# Entrance_v0_2.net
KiCad netlist of a schematic drawn in EAGLE
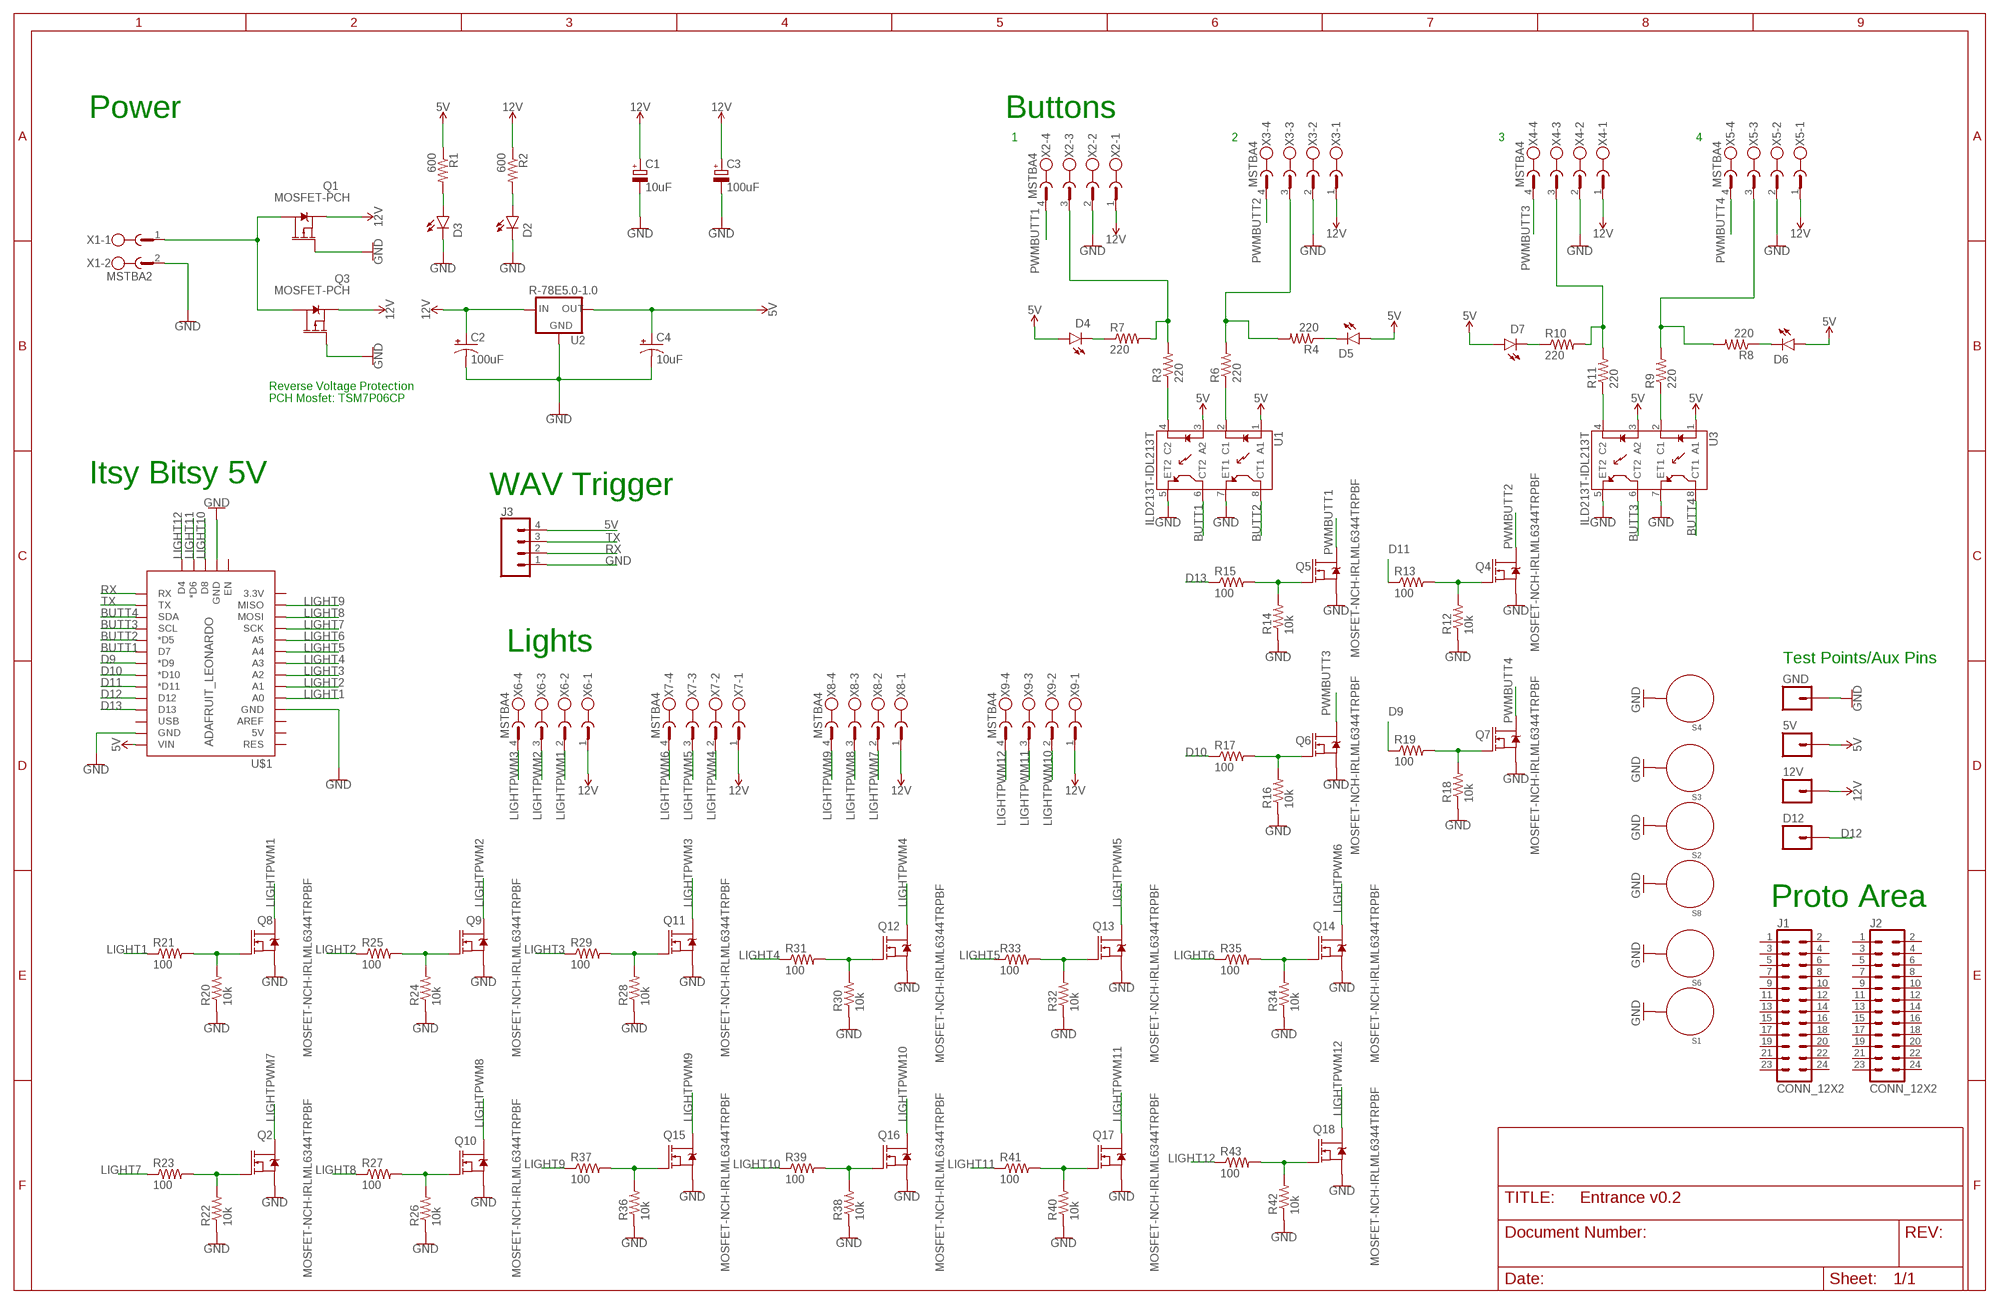
[diagram p0: schematic, sheet 1]

(export (version "E")
  (design (tool "Eeschema 10.0.6"))
  (components
    (comp (ref "5V")
      (value "M01PTH")
      (footprint "eagle-import:1X01")
      (libsource (lib "eagle-import") (part "M01PTH"))
    )
    (comp (ref "12V")
      (value "M01PTH")
      (footprint "eagle-import:1X01")
      (libsource (lib "eagle-import") (part "M01PTH"))
    )
    (comp (ref "C1")
      (value "10uF")
      (footprint "eagle-import:E2-5")
      (libsource (lib "eagle-import") (part "CPOL-EUE2-5"))
    )
    (comp (ref "C2")
      (value "100uF")
      (footprint "eagle-import:CPOL-RADIAL-2.5MM-6.5MM")
      (libsource (lib "eagle-import") (part "100UF-POLAR-RADIAL-2.5MM-25V-20%"))
    )
    (comp (ref "C3")
      (value "100uF")
      (footprint "eagle-import:E3,5-10")
      (libsource (lib "eagle-import") (part "CPOL-EUE3.5-10"))
    )
    (comp (ref "C4")
      (value "10uF")
      (footprint "eagle-import:CPOL-RADIAL-2.5MM-5MM-KIT")
      (libsource (lib "eagle-import") (part "10UF-POLAR-RADIAL-2.5MM-KIT-25V-20%"))
    )
    (comp (ref "D2")
      (value "RED")
      (footprint "eagle-import:SPARKFUN-LED_LED-1206")
      (libsource (lib "eagle-import") (part "SPARKFUN-LED_LED1206"))
    )
    (comp (ref "D3")
      (value "RED")
      (footprint "eagle-import:SPARKFUN-LED_LED-1206")
      (libsource (lib "eagle-import") (part "SPARKFUN-LED_LED1206"))
    )
    (comp (ref "D4")
      (value "RED")
      (footprint "eagle-import:LED-1206")
      (libsource (lib "eagle-import") (part "LED-RED1206"))
    )
    (comp (ref "D5")
      (value "RED")
      (footprint "eagle-import:LED-1206")
      (libsource (lib "eagle-import") (part "LED-RED1206"))
    )
    (comp (ref "D6")
      (value "RED")
      (footprint "eagle-import:LED-1206")
      (libsource (lib "eagle-import") (part "LED-RED1206"))
    )
    (comp (ref "D7")
      (value "RED")
      (footprint "eagle-import:LED-1206")
      (libsource (lib "eagle-import") (part "LED-RED1206"))
    )
    (comp (ref "D12")
      (value "M01PTH")
      (footprint "eagle-import:1X01")
      (libsource (lib "eagle-import") (part "M01PTH"))
    )
    (comp (ref "GND")
      (value "M01PTH")
      (footprint "eagle-import:1X01")
      (libsource (lib "eagle-import") (part "M01PTH"))
    )
    (comp (ref "J1")
      (value "CONN_12X2")
      (footprint "eagle-import:2X12")
      (libsource (lib "eagle-import") (part "CONN_12X2"))
    )
    (comp (ref "J2")
      (value "CONN_12X2")
      (footprint "eagle-import:2X12")
      (libsource (lib "eagle-import") (part "CONN_12X2"))
    )
    (comp (ref "J3")
      (value "CONN_043.5MM_RA")
      (footprint "eagle-import:1X04_3.5MM_RA")
      (libsource (lib "eagle-import") (part "CONN_043.5MM_RA"))
    )
    (comp (ref "Q1")
      (value "MOSFET-PCH")
      (footprint "eagle-import:DPAK@1")
      (libsource (lib "eagle-import") (part "MOSFET-PCH"))
    )
    (comp (ref "Q2")
      (value "MOSFET-NCH-IRLML6344TRPBF")
      (footprint "eagle-import:SOT23-3")
      (libsource (lib "eagle-import") (part "MOSFET-NCH-IRLML6344TRPBF"))
    )
    (comp (ref "Q3")
      (value "MOSFET-PCH")
      (footprint "eagle-import:DPAK@1")
      (libsource (lib "eagle-import") (part "MOSFET-PCH"))
    )
    (comp (ref "Q4")
      (value "MOSFET-NCH-IRLML6344TRPBF")
      (footprint "eagle-import:SOT23-3")
      (libsource (lib "eagle-import") (part "MOSFET-NCH-IRLML6344TRPBF"))
    )
    (comp (ref "Q5")
      (value "MOSFET-NCH-IRLML6344TRPBF")
      (footprint "eagle-import:SOT23-3")
      (libsource (lib "eagle-import") (part "MOSFET-NCH-IRLML6344TRPBF"))
    )
    (comp (ref "Q6")
      (value "MOSFET-NCH-IRLML6344TRPBF")
      (footprint "eagle-import:SOT23-3")
      (libsource (lib "eagle-import") (part "MOSFET-NCH-IRLML6344TRPBF"))
    )
    (comp (ref "Q7")
      (value "MOSFET-NCH-IRLML6344TRPBF")
      (footprint "eagle-import:SOT23-3")
      (libsource (lib "eagle-import") (part "MOSFET-NCH-IRLML6344TRPBF"))
    )
    (comp (ref "Q8")
      (value "MOSFET-NCH-IRLML6344TRPBF")
      (footprint "eagle-import:SOT23-3")
      (libsource (lib "eagle-import") (part "MOSFET-NCH-IRLML6344TRPBF"))
    )
    (comp (ref "Q9")
      (value "MOSFET-NCH-IRLML6344TRPBF")
      (footprint "eagle-import:SOT23-3")
      (libsource (lib "eagle-import") (part "MOSFET-NCH-IRLML6344TRPBF"))
    )
    (comp (ref "Q10")
      (value "MOSFET-NCH-IRLML6344TRPBF")
      (footprint "eagle-import:SOT23-3")
      (libsource (lib "eagle-import") (part "MOSFET-NCH-IRLML6344TRPBF"))
    )
    (comp (ref "Q11")
      (value "MOSFET-NCH-IRLML6344TRPBF")
      (footprint "eagle-import:SOT23-3")
      (libsource (lib "eagle-import") (part "MOSFET-NCH-IRLML6344TRPBF"))
    )
    (comp (ref "Q12")
      (value "MOSFET-NCH-IRLML6344TRPBF")
      (footprint "eagle-import:SOT23-3")
      (libsource (lib "eagle-import") (part "MOSFET-NCH-IRLML6344TRPBF"))
    )
    (comp (ref "Q13")
      (value "MOSFET-NCH-IRLML6344TRPBF")
      (footprint "eagle-import:SOT23-3")
      (libsource (lib "eagle-import") (part "MOSFET-NCH-IRLML6344TRPBF"))
    )
    (comp (ref "Q14")
      (value "MOSFET-NCH-IRLML6344TRPBF")
      (footprint "eagle-import:SOT23-3")
      (libsource (lib "eagle-import") (part "MOSFET-NCH-IRLML6344TRPBF"))
    )
    (comp (ref "Q15")
      (value "MOSFET-NCH-IRLML6344TRPBF")
      (footprint "eagle-import:SOT23-3")
      (libsource (lib "eagle-import") (part "MOSFET-NCH-IRLML6344TRPBF"))
    )
    (comp (ref "Q16")
      (value "MOSFET-NCH-IRLML6344TRPBF")
      (footprint "eagle-import:SOT23-3")
      (libsource (lib "eagle-import") (part "MOSFET-NCH-IRLML6344TRPBF"))
    )
    (comp (ref "Q17")
      (value "MOSFET-NCH-IRLML6344TRPBF")
      (footprint "eagle-import:SOT23-3")
      (libsource (lib "eagle-import") (part "MOSFET-NCH-IRLML6344TRPBF"))
    )
    (comp (ref "Q18")
      (value "MOSFET-NCH-IRLML6344TRPBF")
      (footprint "eagle-import:SOT23-3")
      (libsource (lib "eagle-import") (part "MOSFET-NCH-IRLML6344TRPBF"))
    )
    (comp (ref "R1")
      (value "600")
      (footprint "eagle-import:R0805")
      (libsource (lib "eagle-import") (part "R-US_R0805"))
    )
    (comp (ref "R2")
      (value "600")
      (footprint "eagle-import:R0805")
      (libsource (lib "eagle-import") (part "R-US_R0805"))
    )
    (comp (ref "R3")
      (value "220")
      (footprint "eagle-import:R0805")
      (libsource (lib "eagle-import") (part "R-US_R0805"))
    )
    (comp (ref "R4")
      (value "220")
      (footprint "eagle-import:R0805")
      (libsource (lib "eagle-import") (part "R-US_R0805"))
    )
    (comp (ref "R6")
      (value "220")
      (footprint "eagle-import:R0805")
      (libsource (lib "eagle-import") (part "R-US_R0805"))
    )
    (comp (ref "R7")
      (value "220")
      (footprint "eagle-import:R0805")
      (libsource (lib "eagle-import") (part "R-US_R0805"))
    )
    (comp (ref "R8")
      (value "220")
      (footprint "eagle-import:R0805")
      (libsource (lib "eagle-import") (part "R-US_R0805"))
    )
    (comp (ref "R9")
      (value "220")
      (footprint "eagle-import:R0805")
      (libsource (lib "eagle-import") (part "R-US_R0805"))
    )
    (comp (ref "R10")
      (value "220")
      (footprint "eagle-import:R0805")
      (libsource (lib "eagle-import") (part "R-US_R0805"))
    )
    (comp (ref "R11")
      (value "220")
      (footprint "eagle-import:R0805")
      (libsource (lib "eagle-import") (part "R-US_R0805"))
    )
    (comp (ref "R12")
      (value "10k")
      (footprint "eagle-import:R0805")
      (libsource (lib "eagle-import") (part "R-US_R0805"))
    )
    (comp (ref "R13")
      (value "100")
      (footprint "eagle-import:R0805")
      (libsource (lib "eagle-import") (part "R-US_R0805"))
    )
    (comp (ref "R14")
      (value "10k")
      (footprint "eagle-import:R0805")
      (libsource (lib "eagle-import") (part "R-US_R0805"))
    )
    (comp (ref "R15")
      (value "100")
      (footprint "eagle-import:R0805")
      (libsource (lib "eagle-import") (part "R-US_R0805"))
    )
    (comp (ref "R16")
      (value "10k")
      (footprint "eagle-import:R0805")
      (libsource (lib "eagle-import") (part "R-US_R0805"))
    )
    (comp (ref "R17")
      (value "100")
      (footprint "eagle-import:R0805")
      (libsource (lib "eagle-import") (part "R-US_R0805"))
    )
    (comp (ref "R18")
      (value "10k")
      (footprint "eagle-import:R0805")
      (libsource (lib "eagle-import") (part "R-US_R0805"))
    )
    (comp (ref "R19")
      (value "100")
      (footprint "eagle-import:R0805")
      (libsource (lib "eagle-import") (part "R-US_R0805"))
    )
    (comp (ref "R20")
      (value "10k")
      (footprint "eagle-import:R0805")
      (libsource (lib "eagle-import") (part "R-US_R0805"))
    )
    (comp (ref "R21")
      (value "100")
      (footprint "eagle-import:R0805")
      (libsource (lib "eagle-import") (part "R-US_R0805"))
    )
    (comp (ref "R22")
      (value "10k")
      (footprint "eagle-import:R0805")
      (libsource (lib "eagle-import") (part "R-US_R0805"))
    )
    (comp (ref "R23")
      (value "100")
      (footprint "eagle-import:R0805")
      (libsource (lib "eagle-import") (part "R-US_R0805"))
    )
    (comp (ref "R24")
      (value "10k")
      (footprint "eagle-import:R0805")
      (libsource (lib "eagle-import") (part "R-US_R0805"))
    )
    (comp (ref "R25")
      (value "100")
      (footprint "eagle-import:R0805")
      (libsource (lib "eagle-import") (part "R-US_R0805"))
    )
    (comp (ref "R26")
      (value "10k")
      (footprint "eagle-import:R0805")
      (libsource (lib "eagle-import") (part "R-US_R0805"))
    )
    (comp (ref "R27")
      (value "100")
      (footprint "eagle-import:R0805")
      (libsource (lib "eagle-import") (part "R-US_R0805"))
    )
    (comp (ref "R28")
      (value "10k")
      (footprint "eagle-import:R0805")
      (libsource (lib "eagle-import") (part "R-US_R0805"))
    )
    (comp (ref "R29")
      (value "100")
      (footprint "eagle-import:R0805")
      (libsource (lib "eagle-import") (part "R-US_R0805"))
    )
    (comp (ref "R30")
      (value "10k")
      (footprint "eagle-import:R0805")
      (libsource (lib "eagle-import") (part "R-US_R0805"))
    )
    (comp (ref "R31")
      (value "100")
      (footprint "eagle-import:R0805")
      (libsource (lib "eagle-import") (part "R-US_R0805"))
    )
    (comp (ref "R32")
      (value "10k")
      (footprint "eagle-import:R0805")
      (libsource (lib "eagle-import") (part "R-US_R0805"))
    )
    (comp (ref "R33")
      (value "100")
      (footprint "eagle-import:R0805")
      (libsource (lib "eagle-import") (part "R-US_R0805"))
    )
    (comp (ref "R34")
      (value "10k")
      (footprint "eagle-import:R0805")
      (libsource (lib "eagle-import") (part "R-US_R0805"))
    )
    (comp (ref "R35")
      (value "100")
      (footprint "eagle-import:R0805")
      (libsource (lib "eagle-import") (part "R-US_R0805"))
    )
    (comp (ref "R36")
      (value "10k")
      (footprint "eagle-import:R0805")
      (libsource (lib "eagle-import") (part "R-US_R0805"))
    )
    (comp (ref "R37")
      (value "100")
      (footprint "eagle-import:R0805")
      (libsource (lib "eagle-import") (part "R-US_R0805"))
    )
    (comp (ref "R38")
      (value "10k")
      (footprint "eagle-import:R0805")
      (libsource (lib "eagle-import") (part "R-US_R0805"))
    )
    (comp (ref "R39")
      (value "100")
      (footprint "eagle-import:R0805")
      (libsource (lib "eagle-import") (part "R-US_R0805"))
    )
    (comp (ref "R40")
      (value "10k")
      (footprint "eagle-import:R0805")
      (libsource (lib "eagle-import") (part "R-US_R0805"))
    )
    (comp (ref "R41")
      (value "100")
      (footprint "eagle-import:R0805")
      (libsource (lib "eagle-import") (part "R-US_R0805"))
    )
    (comp (ref "R42")
      (value "10k")
      (footprint "eagle-import:R0805")
      (libsource (lib "eagle-import") (part "R-US_R0805"))
    )
    (comp (ref "R43")
      (value "100")
      (footprint "eagle-import:R0805")
      (libsource (lib "eagle-import") (part "R-US_R0805"))
    )
    (comp (ref "S1")
      (value "STANDOFF_ELECTRICAL5-32")
      (footprint "eagle-import:STANDOFF_ELECTRICAL_5_32")
      (libsource (lib "eagle-import") (part "STANDOFF_ELECTRICAL5-32"))
    )
    (comp (ref "S2")
      (value "STANDOFF_ELECTRICAL5-32")
      (footprint "eagle-import:STANDOFF_ELECTRICAL_5_32")
      (libsource (lib "eagle-import") (part "STANDOFF_ELECTRICAL5-32"))
    )
    (comp (ref "S3")
      (value "STANDOFF_ELECTRICAL5-32")
      (footprint "eagle-import:STANDOFF_ELECTRICAL_5_32")
      (libsource (lib "eagle-import") (part "STANDOFF_ELECTRICAL5-32"))
    )
    (comp (ref "S4")
      (value "STANDOFF_ELECTRICAL5-32")
      (footprint "eagle-import:STANDOFF_ELECTRICAL_5_32")
      (libsource (lib "eagle-import") (part "STANDOFF_ELECTRICAL5-32"))
    )
    (comp (ref "S6")
      (value "STANDOFF_ELECTRICAL5-32")
      (footprint "eagle-import:STANDOFF_ELECTRICAL_5_32")
      (libsource (lib "eagle-import") (part "STANDOFF_ELECTRICAL5-32"))
    )
    (comp (ref "S8")
      (value "STANDOFF_ELECTRICAL5-32")
      (footprint "eagle-import:STANDOFF_ELECTRICAL_5_32")
      (libsource (lib "eagle-import") (part "STANDOFF_ELECTRICAL5-32"))
    )
    (comp (ref "U$1")
      (value "ADAFRUIT_LEONARDO")
      (footprint "eagle-import:ADAFRUIT_LENOARDO")
      (libsource (lib "eagle-import") (part "ADAFRUIT_LEONARDO"))
    )
    (comp (ref "U1")
      (value "ILD213T-IDL213T")
      (footprint "eagle-import:SO08@1")
      (libsource (lib "eagle-import") (part "ILD213T-IDL213T"))
    )
    (comp (ref "U2")
      (value "R-78E5.0-1.0")
      (footprint "eagle-import:DC-DC_CONVERTER_78XX")
      (libsource (lib "eagle-import") (part "R-78E5.0-1.0"))
    )
    (comp (ref "U3")
      (value "ILD213T-IDL213T")
      (footprint "eagle-import:SO08@1")
      (libsource (lib "eagle-import") (part "ILD213T-IDL213T"))
    )
    (comp (ref "X1")
      (value "MSTBA2")
      (footprint "eagle-import:MSTBA2")
      (fields (field (name "MF") "FARNELL") (field (name "MPN") "1757242"))
      (libsource (lib "eagle-import") (part "MSTBA2"))
    )
    (comp (ref "X2")
      (value "MSTBA4")
      (footprint "eagle-import:MSTBA4")
      (fields (field (name "MF") "FARNELL") (field (name "MPN") "1757268"))
      (libsource (lib "eagle-import") (part "MSTBA4"))
    )
    (comp (ref "X3")
      (value "MSTBA4")
      (footprint "eagle-import:MSTBA4")
      (fields (field (name "MF") "FARNELL") (field (name "MPN") "1757268"))
      (libsource (lib "eagle-import") (part "MSTBA4"))
    )
    (comp (ref "X4")
      (value "MSTBA4")
      (footprint "eagle-import:MSTBA4")
      (fields (field (name "MF") "FARNELL") (field (name "MPN") "1757268"))
      (libsource (lib "eagle-import") (part "MSTBA4"))
    )
    (comp (ref "X5")
      (value "MSTBA4")
      (footprint "eagle-import:MSTBA4")
      (fields (field (name "MF") "FARNELL") (field (name "MPN") "1757268"))
      (libsource (lib "eagle-import") (part "MSTBA4"))
    )
    (comp (ref "X6")
      (value "MSTBA4")
      (footprint "eagle-import:MSTBA4")
      (fields (field (name "MF") "FARNELL") (field (name "MPN") "1757268"))
      (libsource (lib "eagle-import") (part "MSTBA4"))
    )
    (comp (ref "X7")
      (value "MSTBA4")
      (footprint "eagle-import:MSTBA4")
      (fields (field (name "MF") "FARNELL") (field (name "MPN") "1757268"))
      (libsource (lib "eagle-import") (part "MSTBA4"))
    )
    (comp (ref "X8")
      (value "MSTBA4")
      (footprint "eagle-import:MSTBA4")
      (fields (field (name "MF") "FARNELL") (field (name "MPN") "1757268"))
      (libsource (lib "eagle-import") (part "MSTBA4"))
    )
    (comp (ref "X9")
      (value "MSTBA4")
      (footprint "eagle-import:MSTBA4")
      (fields (field (name "MF") "FARNELL") (field (name "MPN") "1757268"))
      (libsource (lib "eagle-import") (part "MSTBA4"))
    )
  )
  (nets
    (net (code "1") (name "/BUTT1") (class "Default")
      (node (ref "U$1") (pin "D7") (pinfunction "D7_D7") (pintype "bidirectional"))
      (node (ref "U1") (pin "6") (pinfunction "CT2_6") (pintype "bidirectional"))
    )
    (net (code "2") (name "/BUTT2") (class "Default")
      (node (ref "U$1") (pin "D5") (pinfunction "*D5_D5") (pintype "bidirectional"))
      (node (ref "U1") (pin "8") (pinfunction "CT1_8") (pintype "bidirectional"))
    )
    (net (code "3") (name "/BUTT3") (class "Default")
      (node (ref "U$1") (pin "SCL") (pinfunction "SCL_SCL") (pintype "bidirectional"))
      (node (ref "U3") (pin "6") (pinfunction "CT2_6") (pintype "bidirectional"))
    )
    (net (code "4") (name "/BUTT4") (class "Default")
      (node (ref "U$1") (pin "SDA") (pinfunction "SDA_SDA") (pintype "bidirectional"))
      (node (ref "U3") (pin "8") (pinfunction "CT1_8") (pintype "bidirectional"))
    )
    (net (code "5") (name "/D9") (class "Default")
      (node (ref "R19") (pin "1") (pinfunction "1_1") (pintype "passive"))
      (node (ref "U$1") (pin "D9") (pinfunction "*D9_D9") (pintype "bidirectional"))
    )
    (net (code "6") (name "/D10") (class "Default")
      (node (ref "R17") (pin "1") (pinfunction "1_1") (pintype "passive"))
      (node (ref "U$1") (pin "D10") (pinfunction "*D10_D10") (pintype "bidirectional"))
    )
    (net (code "7") (name "/D11") (class "Default")
      (node (ref "R13") (pin "1") (pinfunction "1_1") (pintype "passive"))
      (node (ref "U$1") (pin "D11") (pinfunction "*D11_D11") (pintype "bidirectional"))
    )
    (net (code "8") (name "/D12") (class "Default")
      (node (ref "D12") (pin "1") (pinfunction "1_1") (pintype "passive"))
      (node (ref "U$1") (pin "D12") (pinfunction "D12_D12") (pintype "bidirectional"))
    )
    (net (code "9") (name "/D13") (class "Default")
      (node (ref "R15") (pin "1") (pinfunction "1_1") (pintype "passive"))
      (node (ref "U$1") (pin "D13") (pinfunction "D13_D13") (pintype "bidirectional"))
    )
    (net (code "10") (name "/LIGHT1") (class "Default")
      (node (ref "R21") (pin "1") (pinfunction "1_1") (pintype "passive"))
      (node (ref "U$1") (pin "A0") (pinfunction "A0_A0") (pintype "bidirectional"))
    )
    (net (code "11") (name "/LIGHT2") (class "Default")
      (node (ref "R25") (pin "1") (pinfunction "1_1") (pintype "passive"))
      (node (ref "U$1") (pin "A1") (pinfunction "A1_A1") (pintype "bidirectional"))
    )
    (net (code "12") (name "/LIGHT3") (class "Default")
      (node (ref "R29") (pin "1") (pinfunction "1_1") (pintype "passive"))
      (node (ref "U$1") (pin "A2") (pinfunction "A2_A2") (pintype "bidirectional"))
    )
    (net (code "13") (name "/LIGHT4") (class "Default")
      (node (ref "R31") (pin "1") (pinfunction "1_1") (pintype "passive"))
      (node (ref "U$1") (pin "A3") (pinfunction "A3_A3") (pintype "bidirectional"))
    )
    (net (code "14") (name "/LIGHT5") (class "Default")
      (node (ref "R33") (pin "1") (pinfunction "1_1") (pintype "passive"))
      (node (ref "U$1") (pin "A4") (pinfunction "A4_A4") (pintype "bidirectional"))
    )
    (net (code "15") (name "/LIGHT6") (class "Default")
      (node (ref "R35") (pin "1") (pinfunction "1_1") (pintype "passive"))
      (node (ref "U$1") (pin "A5") (pinfunction "A5_A5") (pintype "bidirectional"))
    )
    (net (code "16") (name "/LIGHT7") (class "Default")
      (node (ref "R23") (pin "1") (pinfunction "1_1") (pintype "passive"))
      (node (ref "U$1") (pin "SCK") (pinfunction "SCK_SCK") (pintype "bidirectional"))
    )
    (net (code "17") (name "/LIGHT8") (class "Default")
      (node (ref "R27") (pin "1") (pinfunction "1_1") (pintype "passive"))
      (node (ref "U$1") (pin "MOSI") (pinfunction "MOSI_MOSI") (pintype "bidirectional"))
    )
    (net (code "18") (name "/LIGHT9") (class "Default")
      (node (ref "R37") (pin "1") (pinfunction "1_1") (pintype "passive"))
      (node (ref "U$1") (pin "MISO") (pinfunction "MISO_MISO") (pintype "bidirectional"))
    )
    (net (code "19") (name "/LIGHT10") (class "Default")
      (node (ref "R39") (pin "1") (pinfunction "1_1") (pintype "passive"))
      (node (ref "U$1") (pin "D8") (pinfunction "D8_D8") (pintype "bidirectional"))
    )
    (net (code "20") (name "/LIGHT11") (class "Default")
      (node (ref "R41") (pin "1") (pinfunction "1_1") (pintype "passive"))
      (node (ref "U$1") (pin "D6") (pinfunction "*D6_D6") (pintype "bidirectional"))
    )
    (net (code "21") (name "/LIGHT12") (class "Default")
      (node (ref "R43") (pin "1") (pinfunction "1_1") (pintype "passive"))
      (node (ref "U$1") (pin "D4") (pinfunction "D4_D4") (pintype "bidirectional"))
    )
    (net (code "22") (name "/LIGHTPWM1") (class "Default")
      (node (ref "Q8") (pin "3") (pinfunction "D_3") (pintype "bidirectional"))
      (node (ref "X6") (pin "2") (pinfunction "1_2") (pintype "passive"))
    )
    (net (code "23") (name "/LIGHTPWM2") (class "Default")
      (node (ref "Q9") (pin "3") (pinfunction "D_3") (pintype "bidirectional"))
      (node (ref "X6") (pin "3") (pinfunction "1_3") (pintype "passive"))
    )
    (net (code "24") (name "/LIGHTPWM3") (class "Default")
      (node (ref "Q11") (pin "3") (pinfunction "D_3") (pintype "bidirectional"))
      (node (ref "X6") (pin "4") (pinfunction "1_4") (pintype "passive"))
    )
    (net (code "25") (name "/LIGHTPWM4") (class "Default")
      (node (ref "Q12") (pin "3") (pinfunction "D_3") (pintype "bidirectional"))
      (node (ref "X7") (pin "2") (pinfunction "1_2") (pintype "passive"))
    )
    (net (code "26") (name "/LIGHTPWM5") (class "Default")
      (node (ref "Q13") (pin "3") (pinfunction "D_3") (pintype "bidirectional"))
      (node (ref "X7") (pin "3") (pinfunction "1_3") (pintype "passive"))
    )
    (net (code "27") (name "/LIGHTPWM6") (class "Default")
      (node (ref "Q14") (pin "3") (pinfunction "D_3") (pintype "bidirectional"))
      (node (ref "X7") (pin "4") (pinfunction "1_4") (pintype "passive"))
    )
    (net (code "28") (name "/LIGHTPWM7") (class "Default")
      (node (ref "Q2") (pin "3") (pinfunction "D_3") (pintype "bidirectional"))
      (node (ref "X8") (pin "2") (pinfunction "1_2") (pintype "passive"))
    )
    (net (code "29") (name "/LIGHTPWM8") (class "Default")
      (node (ref "Q10") (pin "3") (pinfunction "D_3") (pintype "bidirectional"))
      (node (ref "X8") (pin "3") (pinfunction "1_3") (pintype "passive"))
    )
    (net (code "30") (name "/LIGHTPWM9") (class "Default")
      (node (ref "Q15") (pin "3") (pinfunction "D_3") (pintype "bidirectional"))
      (node (ref "X8") (pin "4") (pinfunction "1_4") (pintype "passive"))
    )
    (net (code "31") (name "/LIGHTPWM10") (class "Default")
      (node (ref "Q16") (pin "3") (pinfunction "D_3") (pintype "bidirectional"))
      (node (ref "X9") (pin "2") (pinfunction "1_2") (pintype "passive"))
    )
    (net (code "32") (name "/LIGHTPWM11") (class "Default")
      (node (ref "Q17") (pin "3") (pinfunction "D_3") (pintype "bidirectional"))
      (node (ref "X9") (pin "3") (pinfunction "1_3") (pintype "passive"))
    )
    (net (code "33") (name "/LIGHTPWM12") (class "Default")
      (node (ref "Q18") (pin "3") (pinfunction "D_3") (pintype "bidirectional"))
      (node (ref "X9") (pin "4") (pinfunction "1_4") (pintype "passive"))
    )
    (net (code "34") (name "/PWMBUTT1") (class "Default")
      (node (ref "Q5") (pin "3") (pinfunction "D_3") (pintype "bidirectional"))
      (node (ref "X2") (pin "4") (pinfunction "1_4") (pintype "passive"))
    )
    (net (code "35") (name "/PWMBUTT2") (class "Default")
      (node (ref "Q4") (pin "3") (pinfunction "D_3") (pintype "bidirectional"))
      (node (ref "X3") (pin "4") (pinfunction "1_4") (pintype "passive"))
    )
    (net (code "36") (name "/PWMBUTT3") (class "Default")
      (node (ref "Q6") (pin "3") (pinfunction "D_3") (pintype "bidirectional"))
      (node (ref "X4") (pin "4") (pinfunction "1_4") (pintype "passive"))
    )
    (net (code "37") (name "/PWMBUTT4") (class "Default")
      (node (ref "Q7") (pin "3") (pinfunction "D_3") (pintype "bidirectional"))
      (node (ref "X5") (pin "4") (pinfunction "1_4") (pintype "passive"))
    )
    (net (code "38") (name "/RX") (class "Default")
      (node (ref "J3") (pin "2") (pinfunction "2_2") (pintype "passive"))
      (node (ref "U$1") (pin "RX") (pinfunction "RX_RX") (pintype "bidirectional"))
    )
    (net (code "39") (name "/TX") (class "Default")
      (node (ref "J3") (pin "3") (pinfunction "3_3") (pintype "passive"))
      (node (ref "U$1") (pin "TX") (pinfunction "TX_TX") (pintype "bidirectional"))
    )
    (net (code "40") (name "5V") (class "Default")
      (node (ref "5V") (pin "1") (pinfunction "1_1") (pintype "passive"))
      (node (ref "C4") (pin "1") (pinfunction "+_1") (pintype "passive"))
      (node (ref "D4") (pin "A") (pinfunction "A_A") (pintype "passive"))
      (node (ref "D5") (pin "A") (pinfunction "A_A") (pintype "passive"))
      (node (ref "D6") (pin "A") (pinfunction "A_A") (pintype "passive"))
      (node (ref "D7") (pin "A") (pinfunction "A_A") (pintype "passive"))
      (node (ref "J3") (pin "4") (pinfunction "4_4") (pintype "passive"))
      (node (ref "R1") (pin "1") (pinfunction "1_1") (pintype "passive"))
      (node (ref "U$1") (pin "VIN") (pinfunction "VIN_VIN") (pintype "bidirectional"))
      (node (ref "U1") (pin "1") (pinfunction "A1_1") (pintype "bidirectional"))
      (node (ref "U1") (pin "3") (pinfunction "A2_3") (pintype "bidirectional"))
      (node (ref "U2") (pin "VOUT") (pinfunction "OUT_VOUT") (pintype "passive"))
      (node (ref "U3") (pin "1") (pinfunction "A1_1") (pintype "bidirectional"))
      (node (ref "U3") (pin "3") (pinfunction "A2_3") (pintype "bidirectional"))
    )
    (net (code "41") (name "12V") (class "Default")
      (node (ref "12V") (pin "1") (pinfunction "1_1") (pintype "passive"))
      (node (ref "C1") (pin "+") (pinfunction "+_+") (pintype "passive"))
      (node (ref "C2") (pin "1") (pinfunction "+_1") (pintype "passive"))
      (node (ref "C3") (pin "+") (pinfunction "+_+") (pintype "passive"))
      (node (ref "Q1") (pin "3") (pinfunction "S_3") (pintype "bidirectional"))
      (node (ref "Q3") (pin "3") (pinfunction "S_3") (pintype "bidirectional"))
      (node (ref "R2") (pin "1") (pinfunction "1_1") (pintype "passive"))
      (node (ref "U2") (pin "VIN") (pinfunction "IN_VIN") (pintype "input"))
      (node (ref "X2") (pin "1") (pinfunction "1_1") (pintype "passive"))
      (node (ref "X3") (pin "1") (pinfunction "1_1") (pintype "passive"))
      (node (ref "X4") (pin "1") (pinfunction "1_1") (pintype "passive"))
      (node (ref "X5") (pin "1") (pinfunction "1_1") (pintype "passive"))
      (node (ref "X6") (pin "1") (pinfunction "1_1") (pintype "passive"))
      (node (ref "X7") (pin "1") (pinfunction "1_1") (pintype "passive"))
      (node (ref "X8") (pin "1") (pinfunction "1_1") (pintype "passive"))
      (node (ref "X9") (pin "1") (pinfunction "1_1") (pintype "passive"))
    )
    (net (code "42") (name "GND") (class "Default")
      (node (ref "C1") (pin "-") (pinfunction "-_-") (pintype "passive"))
      (node (ref "C2") (pin "2") (pinfunction "-_2") (pintype "passive"))
      (node (ref "C3") (pin "-") (pinfunction "-_-") (pintype "passive"))
      (node (ref "C4") (pin "2") (pinfunction "-_2") (pintype "passive"))
      (node (ref "D2") (pin "C") (pinfunction "C_C") (pintype "passive"))
      (node (ref "D3") (pin "C") (pinfunction "C_C") (pintype "passive"))
      (node (ref "GND") (pin "1") (pinfunction "1_1") (pintype "passive"))
      (node (ref "J3") (pin "1") (pinfunction "1_1") (pintype "passive"))
      (node (ref "Q1") (pin "1") (pinfunction "G_1") (pintype "bidirectional"))
      (node (ref "Q10") (pin "2") (pinfunction "S_2") (pintype "bidirectional"))
      (node (ref "Q11") (pin "2") (pinfunction "S_2") (pintype "bidirectional"))
      (node (ref "Q12") (pin "2") (pinfunction "S_2") (pintype "bidirectional"))
      (node (ref "Q13") (pin "2") (pinfunction "S_2") (pintype "bidirectional"))
      (node (ref "Q14") (pin "2") (pinfunction "S_2") (pintype "bidirectional"))
      (node (ref "Q15") (pin "2") (pinfunction "S_2") (pintype "bidirectional"))
      (node (ref "Q16") (pin "2") (pinfunction "S_2") (pintype "bidirectional"))
      (node (ref "Q17") (pin "2") (pinfunction "S_2") (pintype "bidirectional"))
      (node (ref "Q18") (pin "2") (pinfunction "S_2") (pintype "bidirectional"))
      (node (ref "Q2") (pin "2") (pinfunction "S_2") (pintype "bidirectional"))
      (node (ref "Q3") (pin "1") (pinfunction "G_1") (pintype "bidirectional"))
      (node (ref "Q4") (pin "2") (pinfunction "S_2") (pintype "bidirectional"))
      (node (ref "Q5") (pin "2") (pinfunction "S_2") (pintype "bidirectional"))
      (node (ref "Q6") (pin "2") (pinfunction "S_2") (pintype "bidirectional"))
      (node (ref "Q7") (pin "2") (pinfunction "S_2") (pintype "bidirectional"))
      (node (ref "Q8") (pin "2") (pinfunction "S_2") (pintype "bidirectional"))
      (node (ref "Q9") (pin "2") (pinfunction "S_2") (pintype "bidirectional"))
      (node (ref "R12") (pin "1") (pinfunction "1_1") (pintype "passive"))
      (node (ref "R14") (pin "1") (pinfunction "1_1") (pintype "passive"))
      (node (ref "R16") (pin "1") (pinfunction "1_1") (pintype "passive"))
      (node (ref "R18") (pin "1") (pinfunction "1_1") (pintype "passive"))
      (node (ref "R20") (pin "1") (pinfunction "1_1") (pintype "passive"))
      (node (ref "R22") (pin "1") (pinfunction "1_1") (pintype "passive"))
      (node (ref "R24") (pin "1") (pinfunction "1_1") (pintype "passive"))
      (node (ref "R26") (pin "1") (pinfunction "1_1") (pintype "passive"))
      (node (ref "R28") (pin "1") (pinfunction "1_1") (pintype "passive"))
      (node (ref "R30") (pin "1") (pinfunction "1_1") (pintype "passive"))
      (node (ref "R32") (pin "1") (pinfunction "1_1") (pintype "passive"))
      (node (ref "R34") (pin "1") (pinfunction "1_1") (pintype "passive"))
      (node (ref "R36") (pin "1") (pinfunction "1_1") (pintype "passive"))
      (node (ref "R38") (pin "1") (pinfunction "1_1") (pintype "passive"))
      (node (ref "R40") (pin "1") (pinfunction "1_1") (pintype "passive"))
      (node (ref "R42") (pin "1") (pinfunction "1_1") (pintype "passive"))
      (node (ref "S1") (pin "P1") (pinfunction "P$1_P1") (pintype "bidirectional"))
      (node (ref "S2") (pin "P1") (pinfunction "P$1_P1") (pintype "bidirectional"))
      (node (ref "S3") (pin "P1") (pinfunction "P$1_P1") (pintype "bidirectional"))
      (node (ref "S4") (pin "P1") (pinfunction "P$1_P1") (pintype "bidirectional"))
      (node (ref "S6") (pin "P1") (pinfunction "P$1_P1") (pintype "bidirectional"))
      (node (ref "S8") (pin "P1") (pinfunction "P$1_P1") (pintype "bidirectional"))
      (node (ref "U$1") (pin "GND@0") (pinfunction "GND_GND@0") (pintype "bidirectional"))
      (node (ref "U$1") (pin "GND@1") (pinfunction "GND_GND@1") (pintype "bidirectional"))
      (node (ref "U$1") (pin "GND@2") (pinfunction "GND_GND@2") (pintype "bidirectional"))
      (node (ref "U1") (pin "5") (pinfunction "ET2_5") (pintype "bidirectional"))
      (node (ref "U1") (pin "7") (pinfunction "ET1_7") (pintype "bidirectional"))
      (node (ref "U2") (pin "GND") (pinfunction "GND_GND") (pintype "input"))
      (node (ref "U3") (pin "5") (pinfunction "ET2_5") (pintype "bidirectional"))
      (node (ref "U3") (pin "7") (pinfunction "ET1_7") (pintype "bidirectional"))
      (node (ref "X1") (pin "2") (pinfunction "1_2") (pintype "passive"))
      (node (ref "X2") (pin "2") (pinfunction "1_2") (pintype "passive"))
      (node (ref "X3") (pin "2") (pinfunction "1_2") (pintype "passive"))
      (node (ref "X4") (pin "2") (pinfunction "1_2") (pintype "passive"))
      (node (ref "X5") (pin "2") (pinfunction "1_2") (pintype "passive"))
    )
    (net (code "43") (name "Net-(D2-PadA)") (class "Default")
      (node (ref "D2") (pin "A") (pinfunction "A_A") (pintype "passive"))
      (node (ref "R2") (pin "2") (pinfunction "2_2") (pintype "passive"))
    )
    (net (code "44") (name "Net-(D3-PadA)") (class "Default")
      (node (ref "D3") (pin "A") (pinfunction "A_A") (pintype "passive"))
      (node (ref "R1") (pin "2") (pinfunction "2_2") (pintype "passive"))
    )
    (net (code "45") (name "Net-(D4-PadC)") (class "Default")
      (node (ref "D4") (pin "C") (pinfunction "C_C") (pintype "passive"))
      (node (ref "R7") (pin "1") (pinfunction "1_1") (pintype "passive"))
    )
    (net (code "46") (name "Net-(D5-PadC)") (class "Default")
      (node (ref "D5") (pin "C") (pinfunction "C_C") (pintype "passive"))
      (node (ref "R4") (pin "1") (pinfunction "1_1") (pintype "passive"))
    )
    (net (code "47") (name "Net-(D6-PadC)") (class "Default")
      (node (ref "D6") (pin "C") (pinfunction "C_C") (pintype "passive"))
      (node (ref "R8") (pin "1") (pinfunction "1_1") (pintype "passive"))
    )
    (net (code "48") (name "Net-(D7-PadC)") (class "Default")
      (node (ref "D7") (pin "C") (pinfunction "C_C") (pintype "passive"))
      (node (ref "R10") (pin "1") (pinfunction "1_1") (pintype "passive"))
    )
    (net (code "49") (name "Net-(Q1-D)") (class "Default")
      (node (ref "Q1") (pin "4") (pinfunction "D_4") (pintype "bidirectional"))
      (node (ref "Q3") (pin "4") (pinfunction "D_4") (pintype "bidirectional"))
      (node (ref "X1") (pin "1") (pinfunction "1_1") (pintype "passive"))
    )
    (net (code "50") (name "Net-(Q2-G)") (class "Default")
      (node (ref "Q2") (pin "1") (pinfunction "G_1") (pintype "bidirectional"))
      (node (ref "R22") (pin "2") (pinfunction "2_2") (pintype "passive"))
      (node (ref "R23") (pin "2") (pinfunction "2_2") (pintype "passive"))
    )
    (net (code "51") (name "Net-(Q4-G)") (class "Default")
      (node (ref "Q4") (pin "1") (pinfunction "G_1") (pintype "bidirectional"))
      (node (ref "R12") (pin "2") (pinfunction "2_2") (pintype "passive"))
      (node (ref "R13") (pin "2") (pinfunction "2_2") (pintype "passive"))
    )
    (net (code "52") (name "Net-(Q5-G)") (class "Default")
      (node (ref "Q5") (pin "1") (pinfunction "G_1") (pintype "bidirectional"))
      (node (ref "R14") (pin "2") (pinfunction "2_2") (pintype "passive"))
      (node (ref "R15") (pin "2") (pinfunction "2_2") (pintype "passive"))
    )
    (net (code "53") (name "Net-(Q6-G)") (class "Default")
      (node (ref "Q6") (pin "1") (pinfunction "G_1") (pintype "bidirectional"))
      (node (ref "R16") (pin "2") (pinfunction "2_2") (pintype "passive"))
      (node (ref "R17") (pin "2") (pinfunction "2_2") (pintype "passive"))
    )
    (net (code "54") (name "Net-(Q7-G)") (class "Default")
      (node (ref "Q7") (pin "1") (pinfunction "G_1") (pintype "bidirectional"))
      (node (ref "R18") (pin "2") (pinfunction "2_2") (pintype "passive"))
      (node (ref "R19") (pin "2") (pinfunction "2_2") (pintype "passive"))
    )
    (net (code "55") (name "Net-(Q8-G)") (class "Default")
      (node (ref "Q8") (pin "1") (pinfunction "G_1") (pintype "bidirectional"))
      (node (ref "R20") (pin "2") (pinfunction "2_2") (pintype "passive"))
      (node (ref "R21") (pin "2") (pinfunction "2_2") (pintype "passive"))
    )
    (net (code "56") (name "Net-(Q9-G)") (class "Default")
      (node (ref "Q9") (pin "1") (pinfunction "G_1") (pintype "bidirectional"))
      (node (ref "R24") (pin "2") (pinfunction "2_2") (pintype "passive"))
      (node (ref "R25") (pin "2") (pinfunction "2_2") (pintype "passive"))
    )
    (net (code "57") (name "Net-(Q10-G)") (class "Default")
      (node (ref "Q10") (pin "1") (pinfunction "G_1") (pintype "bidirectional"))
      (node (ref "R26") (pin "2") (pinfunction "2_2") (pintype "passive"))
      (node (ref "R27") (pin "2") (pinfunction "2_2") (pintype "passive"))
    )
    (net (code "58") (name "Net-(Q11-G)") (class "Default")
      (node (ref "Q11") (pin "1") (pinfunction "G_1") (pintype "bidirectional"))
      (node (ref "R28") (pin "2") (pinfunction "2_2") (pintype "passive"))
      (node (ref "R29") (pin "2") (pinfunction "2_2") (pintype "passive"))
    )
    (net (code "59") (name "Net-(Q12-G)") (class "Default")
      (node (ref "Q12") (pin "1") (pinfunction "G_1") (pintype "bidirectional"))
      (node (ref "R30") (pin "2") (pinfunction "2_2") (pintype "passive"))
      (node (ref "R31") (pin "2") (pinfunction "2_2") (pintype "passive"))
    )
    (net (code "60") (name "Net-(Q13-G)") (class "Default")
      (node (ref "Q13") (pin "1") (pinfunction "G_1") (pintype "bidirectional"))
      (node (ref "R32") (pin "2") (pinfunction "2_2") (pintype "passive"))
      (node (ref "R33") (pin "2") (pinfunction "2_2") (pintype "passive"))
    )
    (net (code "61") (name "Net-(Q14-G)") (class "Default")
      (node (ref "Q14") (pin "1") (pinfunction "G_1") (pintype "bidirectional"))
      (node (ref "R34") (pin "2") (pinfunction "2_2") (pintype "passive"))
      (node (ref "R35") (pin "2") (pinfunction "2_2") (pintype "passive"))
    )
    (net (code "62") (name "Net-(Q15-G)") (class "Default")
      (node (ref "Q15") (pin "1") (pinfunction "G_1") (pintype "bidirectional"))
      (node (ref "R36") (pin "2") (pinfunction "2_2") (pintype "passive"))
      (node (ref "R37") (pin "2") (pinfunction "2_2") (pintype "passive"))
    )
    (net (code "63") (name "Net-(Q16-G)") (class "Default")
      (node (ref "Q16") (pin "1") (pinfunction "G_1") (pintype "bidirectional"))
      (node (ref "R38") (pin "2") (pinfunction "2_2") (pintype "passive"))
      (node (ref "R39") (pin "2") (pinfunction "2_2") (pintype "passive"))
    )
    (net (code "64") (name "Net-(Q17-G)") (class "Default")
      (node (ref "Q17") (pin "1") (pinfunction "G_1") (pintype "bidirectional"))
      (node (ref "R40") (pin "2") (pinfunction "2_2") (pintype "passive"))
      (node (ref "R41") (pin "2") (pinfunction "2_2") (pintype "passive"))
    )
    (net (code "65") (name "Net-(Q18-G)") (class "Default")
      (node (ref "Q18") (pin "1") (pinfunction "G_1") (pintype "bidirectional"))
      (node (ref "R42") (pin "2") (pinfunction "2_2") (pintype "passive"))
      (node (ref "R43") (pin "2") (pinfunction "2_2") (pintype "passive"))
    )
    (net (code "66") (name "Net-(U1-C1)") (class "Default")
      (node (ref "R6") (pin "1") (pinfunction "1_1") (pintype "passive"))
      (node (ref "U1") (pin "2") (pinfunction "C1_2") (pintype "bidirectional"))
    )
    (net (code "67") (name "Net-(U1-C2)") (class "Default")
      (node (ref "R3") (pin "1") (pinfunction "1_1") (pintype "passive"))
      (node (ref "U1") (pin "4") (pinfunction "C2_4") (pintype "bidirectional"))
    )
    (net (code "68") (name "Net-(U3-C1)") (class "Default")
      (node (ref "R9") (pin "1") (pinfunction "1_1") (pintype "passive"))
      (node (ref "U3") (pin "2") (pinfunction "C1_2") (pintype "bidirectional"))
    )
    (net (code "69") (name "Net-(U3-C2)") (class "Default")
      (node (ref "R11") (pin "1") (pinfunction "1_1") (pintype "passive"))
      (node (ref "U3") (pin "4") (pinfunction "C2_4") (pintype "bidirectional"))
    )
    (net (code "70") (name "Net-(X2C-1)") (class "Default")
      (node (ref "R3") (pin "2") (pinfunction "2_2") (pintype "passive"))
      (node (ref "R7") (pin "2") (pinfunction "2_2") (pintype "passive"))
      (node (ref "X2") (pin "3") (pinfunction "1_3") (pintype "passive"))
    )
    (net (code "71") (name "Net-(X3C-1)") (class "Default")
      (node (ref "R4") (pin "2") (pinfunction "2_2") (pintype "passive"))
      (node (ref "R6") (pin "2") (pinfunction "2_2") (pintype "passive"))
      (node (ref "X3") (pin "3") (pinfunction "1_3") (pintype "passive"))
    )
    (net (code "72") (name "Net-(X4C-1)") (class "Default")
      (node (ref "R10") (pin "2") (pinfunction "2_2") (pintype "passive"))
      (node (ref "R11") (pin "2") (pinfunction "2_2") (pintype "passive"))
      (node (ref "X4") (pin "3") (pinfunction "1_3") (pintype "passive"))
    )
    (net (code "73") (name "Net-(X5C-1)") (class "Default")
      (node (ref "R8") (pin "2") (pinfunction "2_2") (pintype "passive"))
      (node (ref "R9") (pin "2") (pinfunction "2_2") (pintype "passive"))
      (node (ref "X5") (pin "3") (pinfunction "1_3") (pintype "passive"))
    )
    (net (code "74") (name "unconnected-(J1-Pad1)") (class "Default")
      (node (ref "J1") (pin "1") (pinfunction "1_1") (pintype "passive"))
    )
    (net (code "75") (name "unconnected-(J1-Pad2)") (class "Default")
      (node (ref "J1") (pin "2") (pinfunction "2_2") (pintype "passive"))
    )
    (net (code "76") (name "unconnected-(J1-Pad3)") (class "Default")
      (node (ref "J1") (pin "3") (pinfunction "3_3") (pintype "passive"))
    )
    (net (code "77") (name "unconnected-(J1-Pad4)") (class "Default")
      (node (ref "J1") (pin "4") (pinfunction "4_4") (pintype "passive"))
    )
    (net (code "78") (name "unconnected-(J1-Pad5)") (class "Default")
      (node (ref "J1") (pin "5") (pinfunction "5_5") (pintype "passive"))
    )
    (net (code "79") (name "unconnected-(J1-Pad6)") (class "Default")
      (node (ref "J1") (pin "6") (pinfunction "6_6") (pintype "passive"))
    )
    (net (code "80") (name "unconnected-(J1-Pad7)") (class "Default")
      (node (ref "J1") (pin "7") (pinfunction "7_7") (pintype "passive"))
    )
    (net (code "81") (name "unconnected-(J1-Pad8)") (class "Default")
      (node (ref "J1") (pin "8") (pinfunction "8_8") (pintype "passive"))
    )
    (net (code "82") (name "unconnected-(J1-Pad9)") (class "Default")
      (node (ref "J1") (pin "9") (pinfunction "9_9") (pintype "passive"))
    )
    (net (code "83") (name "unconnected-(J1-Pad10)") (class "Default")
      (node (ref "J1") (pin "10") (pinfunction "10_10") (pintype "passive"))
    )
    (net (code "84") (name "unconnected-(J1-Pad11)") (class "Default")
      (node (ref "J1") (pin "11") (pinfunction "11_11") (pintype "passive"))
    )
    (net (code "85") (name "unconnected-(J1-Pad12)") (class "Default")
      (node (ref "J1") (pin "12") (pinfunction "12_12") (pintype "passive"))
    )
    (net (code "86") (name "unconnected-(J1-Pad13)") (class "Default")
      (node (ref "J1") (pin "13") (pinfunction "13_13") (pintype "passive"))
    )
    (net (code "87") (name "unconnected-(J1-Pad14)") (class "Default")
      (node (ref "J1") (pin "14") (pinfunction "14_14") (pintype "passive"))
    )
    (net (code "88") (name "unconnected-(J1-Pad15)") (class "Default")
      (node (ref "J1") (pin "15") (pinfunction "15_15") (pintype "passive"))
    )
    (net (code "89") (name "unconnected-(J1-Pad16)") (class "Default")
      (node (ref "J1") (pin "16") (pinfunction "16_16") (pintype "passive"))
    )
    (net (code "90") (name "unconnected-(J1-Pad17)") (class "Default")
      (node (ref "J1") (pin "17") (pinfunction "17_17") (pintype "passive"))
    )
    (net (code "91") (name "unconnected-(J1-Pad18)") (class "Default")
      (node (ref "J1") (pin "18") (pinfunction "18_18") (pintype "passive"))
    )
    (net (code "92") (name "unconnected-(J1-Pad19)") (class "Default")
      (node (ref "J1") (pin "19") (pinfunction "19_19") (pintype "passive"))
    )
    (net (code "93") (name "unconnected-(J1-Pad20)") (class "Default")
      (node (ref "J1") (pin "20") (pinfunction "20_20") (pintype "passive"))
    )
    (net (code "94") (name "unconnected-(J1-Pad21)") (class "Default")
      (node (ref "J1") (pin "21") (pinfunction "21_21") (pintype "passive"))
    )
    (net (code "95") (name "unconnected-(J1-Pad22)") (class "Default")
      (node (ref "J1") (pin "22") (pinfunction "22_22") (pintype "passive"))
    )
    (net (code "96") (name "unconnected-(J1-Pad23)") (class "Default")
      (node (ref "J1") (pin "23") (pinfunction "23_23") (pintype "passive"))
    )
    (net (code "97") (name "unconnected-(J1-Pad24)") (class "Default")
      (node (ref "J1") (pin "24") (pinfunction "24_24") (pintype "passive"))
    )
    (net (code "98") (name "unconnected-(J2-Pad1)") (class "Default")
      (node (ref "J2") (pin "1") (pinfunction "1_1") (pintype "passive"))
    )
    (net (code "99") (name "unconnected-(J2-Pad2)") (class "Default")
      (node (ref "J2") (pin "2") (pinfunction "2_2") (pintype "passive"))
    )
    (net (code "100") (name "unconnected-(J2-Pad3)") (class "Default")
      (node (ref "J2") (pin "3") (pinfunction "3_3") (pintype "passive"))
    )
    (net (code "101") (name "unconnected-(J2-Pad4)") (class "Default")
      (node (ref "J2") (pin "4") (pinfunction "4_4") (pintype "passive"))
    )
    (net (code "102") (name "unconnected-(J2-Pad5)") (class "Default")
      (node (ref "J2") (pin "5") (pinfunction "5_5") (pintype "passive"))
    )
    (net (code "103") (name "unconnected-(J2-Pad6)") (class "Default")
      (node (ref "J2") (pin "6") (pinfunction "6_6") (pintype "passive"))
    )
    (net (code "104") (name "unconnected-(J2-Pad7)") (class "Default")
      (node (ref "J2") (pin "7") (pinfunction "7_7") (pintype "passive"))
    )
    (net (code "105") (name "unconnected-(J2-Pad8)") (class "Default")
      (node (ref "J2") (pin "8") (pinfunction "8_8") (pintype "passive"))
    )
    (net (code "106") (name "unconnected-(J2-Pad9)") (class "Default")
      (node (ref "J2") (pin "9") (pinfunction "9_9") (pintype "passive"))
    )
    (net (code "107") (name "unconnected-(J2-Pad10)") (class "Default")
      (node (ref "J2") (pin "10") (pinfunction "10_10") (pintype "passive"))
    )
    (net (code "108") (name "unconnected-(J2-Pad11)") (class "Default")
      (node (ref "J2") (pin "11") (pinfunction "11_11") (pintype "passive"))
    )
    (net (code "109") (name "unconnected-(J2-Pad12)") (class "Default")
      (node (ref "J2") (pin "12") (pinfunction "12_12") (pintype "passive"))
    )
    (net (code "110") (name "unconnected-(J2-Pad13)") (class "Default")
      (node (ref "J2") (pin "13") (pinfunction "13_13") (pintype "passive"))
    )
    (net (code "111") (name "unconnected-(J2-Pad14)") (class "Default")
      (node (ref "J2") (pin "14") (pinfunction "14_14") (pintype "passive"))
    )
    (net (code "112") (name "unconnected-(J2-Pad15)") (class "Default")
      (node (ref "J2") (pin "15") (pinfunction "15_15") (pintype "passive"))
    )
    (net (code "113") (name "unconnected-(J2-Pad16)") (class "Default")
      (node (ref "J2") (pin "16") (pinfunction "16_16") (pintype "passive"))
    )
    (net (code "114") (name "unconnected-(J2-Pad17)") (class "Default")
      (node (ref "J2") (pin "17") (pinfunction "17_17") (pintype "passive"))
    )
    (net (code "115") (name "unconnected-(J2-Pad18)") (class "Default")
      (node (ref "J2") (pin "18") (pinfunction "18_18") (pintype "passive"))
    )
    (net (code "116") (name "unconnected-(J2-Pad19)") (class "Default")
      (node (ref "J2") (pin "19") (pinfunction "19_19") (pintype "passive"))
    )
    (net (code "117") (name "unconnected-(J2-Pad20)") (class "Default")
      (node (ref "J2") (pin "20") (pinfunction "20_20") (pintype "passive"))
    )
    (net (code "118") (name "unconnected-(J2-Pad21)") (class "Default")
      (node (ref "J2") (pin "21") (pinfunction "21_21") (pintype "passive"))
    )
    (net (code "119") (name "unconnected-(J2-Pad22)") (class "Default")
      (node (ref "J2") (pin "22") (pinfunction "22_22") (pintype "passive"))
    )
    (net (code "120") (name "unconnected-(J2-Pad23)") (class "Default")
      (node (ref "J2") (pin "23") (pinfunction "23_23") (pintype "passive"))
    )
    (net (code "121") (name "unconnected-(J2-Pad24)") (class "Default")
      (node (ref "J2") (pin "24") (pinfunction "24_24") (pintype "passive"))
    )
    (net (code "122") (name "unconnected-(U$1-3.3V-Pad3V)") (class "Default")
      (node (ref "U$1") (pin "3V") (pinfunction "3.3V_3V") (pintype "bidirectional"))
    )
    (net (code "123") (name "unconnected-(U$1-Pad5V)") (class "Default")
      (node (ref "U$1") (pin "5V") (pinfunction "5V_5V") (pintype "bidirectional"))
    )
    (net (code "124") (name "unconnected-(U$1-PadAREF)") (class "Default")
      (node (ref "U$1") (pin "AREF") (pinfunction "AREF_AREF") (pintype "bidirectional"))
    )
    (net (code "125") (name "unconnected-(U$1-PadEN)") (class "Default")
      (node (ref "U$1") (pin "EN") (pinfunction "EN_EN") (pintype "bidirectional"))
    )
    (net (code "126") (name "unconnected-(U$1-PadRES)") (class "Default")
      (node (ref "U$1") (pin "RES") (pinfunction "RES_RES") (pintype "bidirectional"))
    )
    (net (code "127") (name "unconnected-(U$1-PadUSB)") (class "Default")
      (node (ref "U$1") (pin "USB") (pinfunction "USB_USB") (pintype "bidirectional"))
    )
  )
)
